# Umgebungssensor_PCB.net
KiCad netlist of a schematic drawn in Altium Designer
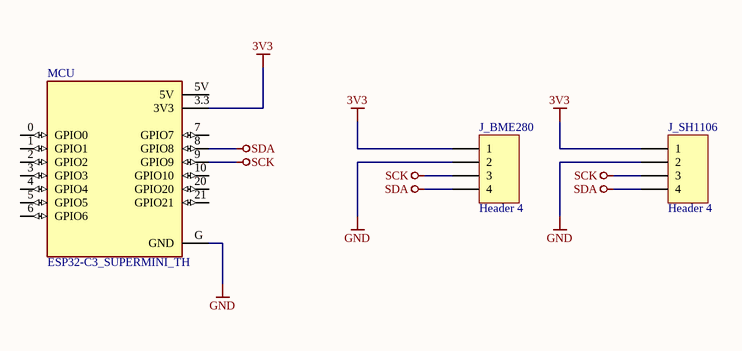
[diagram p0: Umgebungssensor_PCB.SchDoc]

(export (version "E")
  (design (tool "Eeschema 10.0.6"))
  (components
    (comp (ref "J_BME280")
      (value "Header 4")
      (footprint "HDR1X4")
      (description "Header, 4-Pin")
      (fields (field (name "PUBLISHER") "Altium Limited"))
      (libsource (lib "Miscellaneous Connectors") (part "Header 4"))
    )
    (comp (ref "J_SH1106")
      (value "Header 4")
      (footprint "HDR1X4")
      (description "Header, 4-Pin")
      (fields (field (name "PUBLISHER") "Altium Limited"))
      (libsource (lib "Miscellaneous Connectors") (part "Header 4"))
    )
    (comp (ref "MCU")
      (value "ESP32-C3_SUPERMINI_TH")
      (footprint "MODULE_ESP32-C3_SUPERMINI")
      (description "Super tiny ESP32-C3 board")
      (fields (field (name "MF") "Espressif Systems") (field (name "MP") "ESP32-C3 SuperMini_TH"))
      (libsource (lib "ESP32-C3_SUPERMINI_TH") (part "ESP32-C3_SUPERMINI_TH"))
    )
  )
  (nets
    (net (code "1") (name "3V3") (class "Default")
      (node (ref "J_BME280") (pin "1") (pinfunction "1_1") (pintype "passive"))
      (node (ref "J_SH1106") (pin "1") (pinfunction "1_1") (pintype "passive"))
      (node (ref "MCU") (pin "3.3") (pinfunction "3V3_3.3") (pintype "power_in"))
    )
    (net (code "2") (name "GND") (class "Default")
      (node (ref "J_BME280") (pin "2") (pinfunction "2_2") (pintype "passive"))
      (node (ref "J_SH1106") (pin "2") (pinfunction "2_2") (pintype "passive"))
      (node (ref "MCU") (pin "G") (pinfunction "GND_G") (pintype "power_in"))
    )
    (net (code "3") (name "SCK") (class "Default")
      (node (ref "J_BME280") (pin "3") (pinfunction "3_3") (pintype "passive"))
      (node (ref "J_SH1106") (pin "3") (pinfunction "3_3") (pintype "passive"))
      (node (ref "MCU") (pin "9") (pinfunction "GPIO9_9") (pintype "bidirectional"))
    )
    (net (code "4") (name "SDA") (class "Default")
      (node (ref "J_BME280") (pin "4") (pinfunction "4_4") (pintype "passive"))
      (node (ref "J_SH1106") (pin "4") (pinfunction "4_4") (pintype "passive"))
      (node (ref "MCU") (pin "8") (pinfunction "GPIO8_8") (pintype "bidirectional"))
    )
    (net (code "5") (name "unconnected-(MCU-GPIO0-Pad0)") (class "Default")
      (node (ref "MCU") (pin "0") (pinfunction "GPIO0_0") (pintype "bidirectional"))
    )
    (net (code "6") (name "unconnected-(MCU-GPIO1-Pad1)") (class "Default")
      (node (ref "MCU") (pin "1") (pinfunction "GPIO1_1") (pintype "bidirectional"))
    )
    (net (code "7") (name "unconnected-(MCU-GPIO2-Pad2)") (class "Default")
      (node (ref "MCU") (pin "2") (pinfunction "GPIO2_2") (pintype "bidirectional"))
    )
    (net (code "8") (name "unconnected-(MCU-GPIO3-Pad3)") (class "Default")
      (node (ref "MCU") (pin "3") (pinfunction "GPIO3_3") (pintype "bidirectional"))
    )
    (net (code "9") (name "unconnected-(MCU-GPIO4-Pad4)") (class "Default")
      (node (ref "MCU") (pin "4") (pinfunction "GPIO4_4") (pintype "bidirectional"))
    )
    (net (code "10") (name "unconnected-(MCU-GPIO5-Pad5)") (class "Default")
      (node (ref "MCU") (pin "5") (pinfunction "GPIO5_5") (pintype "bidirectional"))
    )
    (net (code "11") (name "unconnected-(MCU-GPIO6-Pad6)") (class "Default")
      (node (ref "MCU") (pin "6") (pinfunction "GPIO6_6") (pintype "bidirectional"))
    )
    (net (code "12") (name "unconnected-(MCU-GPIO7-Pad7)") (class "Default")
      (node (ref "MCU") (pin "7") (pinfunction "GPIO7_7") (pintype "bidirectional"))
    )
    (net (code "13") (name "unconnected-(MCU-GPIO10-Pad10)") (class "Default")
      (node (ref "MCU") (pin "10") (pinfunction "GPIO10_10") (pintype "bidirectional"))
    )
    (net (code "14") (name "unconnected-(MCU-GPIO20-Pad20)") (class "Default")
      (node (ref "MCU") (pin "20") (pinfunction "GPIO20_20") (pintype "bidirectional"))
    )
    (net (code "15") (name "unconnected-(MCU-GPIO21-Pad21)") (class "Default")
      (node (ref "MCU") (pin "21") (pinfunction "GPIO21_21") (pintype "bidirectional"))
    )
    (net (code "16") (name "unconnected-(MCU-Pad5V)") (class "Default")
      (node (ref "MCU") (pin "5V") (pinfunction "5V_5V") (pintype "power_in"))
    )
  )
)
